# gtop.net
KiCad netlist of a schematic drawn in EAGLE
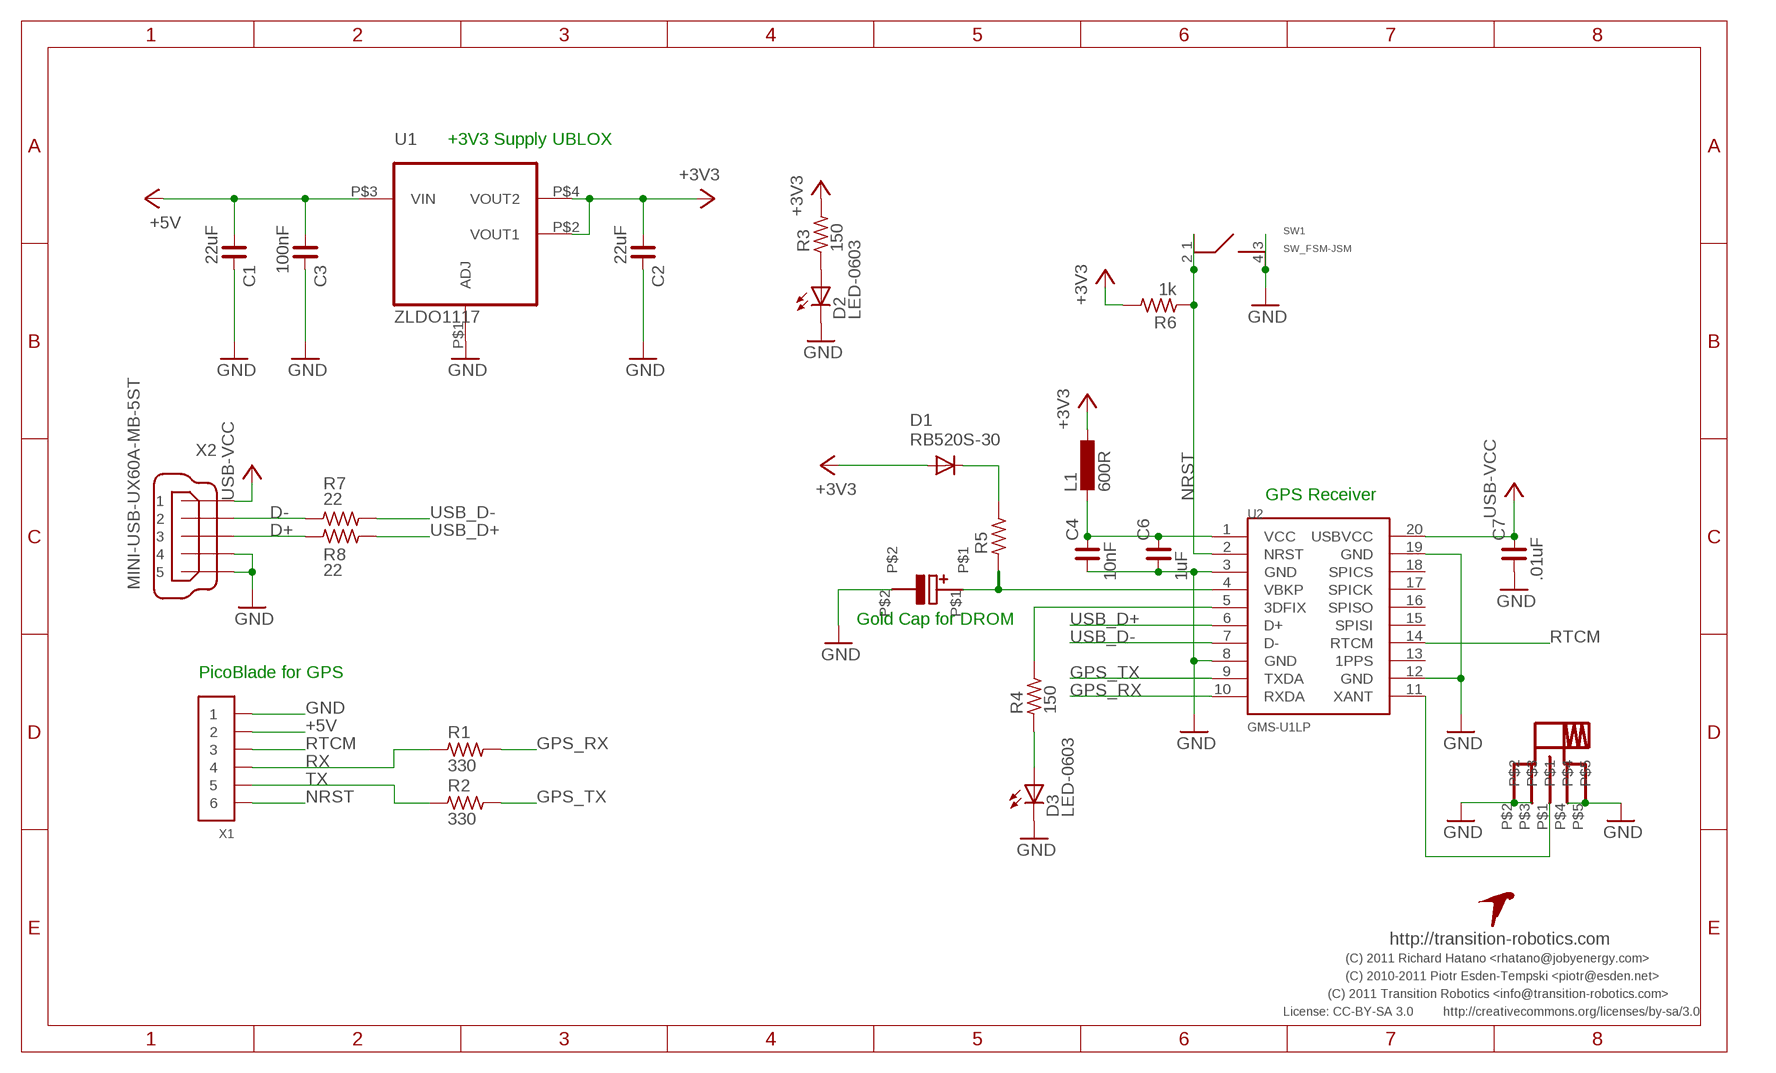
[diagram p0: schematic, sheet 1]

(export (version "E")
  (design (tool "Eeschema 10.0.6"))
  (components
    (comp (ref "C1")
      (value "22uF")
      (footprint "eagle-import:C0805")
      (libsource (lib "eagle-import") (part "C_0805"))
    )
    (comp (ref "C2")
      (value "22uF")
      (footprint "eagle-import:C0805")
      (libsource (lib "eagle-import") (part "C_0805"))
    )
    (comp (ref "C3")
      (value "100nF")
      (footprint "eagle-import:C0805")
      (libsource (lib "eagle-import") (part "C_0805"))
    )
    (comp (ref "C4")
      (value "10nF")
      (footprint "eagle-import:C0603")
      (libsource (lib "eagle-import") (part "C_0603"))
    )
    (comp (ref "C5")
      (value "EECEN0F204AK")
      (footprint "eagle-import:EECEN0F204AK")
      (libsource (lib "eagle-import") (part "EECEN0F204AK"))
    )
    (comp (ref "C6")
      (value "1uF")
      (footprint "eagle-import:C0603")
      (libsource (lib "eagle-import") (part "C_0603"))
    )
    (comp (ref "C7")
      (value ".01uF")
      (footprint "eagle-import:C0603")
      (libsource (lib "eagle-import") (part "C_0603"))
    )
    (comp (ref "D1")
      (value "RB520S-30")
      (footprint "eagle-import:SOD523-DIO")
      (libsource (lib "eagle-import") (part "DIODE"))
    )
    (comp (ref "D2")
      (value "LED-0603")
      (footprint "eagle-import:0603-LED")
      (libsource (lib "eagle-import") (part "LED-0603"))
    )
    (comp (ref "D3")
      (value "LED-0603")
      (footprint "eagle-import:0603-LED")
      (libsource (lib "eagle-import") (part "LED-0603"))
    )
    (comp (ref "J1")
      (value "JOBY_ROBOTICS_SMA")
      (footprint "eagle-import:JOBY_ROBOTICS_SMA")
      (libsource (lib "eagle-import") (part "JOBY_ROBOTICS_SMA"))
    )
    (comp (ref "L1")
      (value "600R")
      (footprint "eagle-import:0603-IND")
      (libsource (lib "eagle-import") (part "INDUCTOR-0603"))
    )
    (comp (ref "R1")
      (value "330")
      (footprint "eagle-import:R0603")
      (libsource (lib "eagle-import") (part "R_0603"))
    )
    (comp (ref "R2")
      (value "330")
      (footprint "eagle-import:R0603")
      (libsource (lib "eagle-import") (part "R_0603"))
    )
    (comp (ref "R3")
      (value "150")
      (footprint "eagle-import:R0603")
      (libsource (lib "eagle-import") (part "R_0603"))
    )
    (comp (ref "R4")
      (value "150")
      (footprint "eagle-import:R0603")
      (libsource (lib "eagle-import") (part "R_0603"))
    )
    (comp (ref "R5")
      (value "R_0603")
      (footprint "eagle-import:R0603")
      (libsource (lib "eagle-import") (part "R_0603"))
    )
    (comp (ref "R6")
      (value "1k")
      (footprint "eagle-import:R0603")
      (libsource (lib "eagle-import") (part "R_0603"))
    )
    (comp (ref "R7")
      (value "22")
      (footprint "eagle-import:R0603")
      (libsource (lib "eagle-import") (part "R_0603"))
    )
    (comp (ref "R8")
      (value "22")
      (footprint "eagle-import:R0603")
      (libsource (lib "eagle-import") (part "R_0603"))
    )
    (comp (ref "SW1")
      (value "SW_FSM-JSM")
      (footprint "eagle-import:SW-FSM_JSM")
      (libsource (lib "eagle-import") (part "SW_FSM-JSM"))
    )
    (comp (ref "U$3")
      (value "TR-LOGO")
      (footprint "eagle-import:TR-LOGO")
      (libsource (lib "eagle-import") (part "TR-LOGO"))
    )
    (comp (ref "U1")
      (value "ZLDO1117")
      (footprint "eagle-import:ZLDO1117")
      (libsource (lib "eagle-import") (part "ZLDO1117"))
    )
    (comp (ref "U2")
      (value "GMS-U1LP")
      (footprint "eagle-import:GMS-U1LP")
      (libsource (lib "eagle-import") (part "GMS-U1LP"))
    )
    (comp (ref "X1")
      (value "CONN_6-1-53261")
      (footprint "eagle-import:PB-53261-06")
      (libsource (lib "eagle-import") (part "CONN_6-1-53261"))
    )
    (comp (ref "X2")
      (value "MINI-USB-UX60A-MB-5ST")
      (footprint "eagle-import:UX60A-MB-5ST")
      (libsource (lib "eagle-import") (part "MINI-USB-UX60A-MB-5ST"))
    )
  )
  (nets
    (net (code "1") (name "+3V3") (class "Default")
      (node (ref "C2") (pin "1") (pinfunction "1_1") (pintype "passive"))
      (node (ref "D1") (pin "2") (pinfunction "A_2") (pintype "passive"))
      (node (ref "L1") (pin "P$1") (pinfunction "1_P$1") (pintype "passive"))
      (node (ref "R3") (pin "2") (pinfunction "2_2") (pintype "passive"))
      (node (ref "R6") (pin "2") (pinfunction "2_2") (pintype "passive"))
      (node (ref "U1") (pin "P$2") (pinfunction "VOUT1_P$2") (pintype "bidirectional"))
      (node (ref "U1") (pin "P$4") (pinfunction "VOUT2_P$4") (pintype "bidirectional"))
    )
    (net (code "2") (name "+5V") (class "Default")
      (node (ref "C1") (pin "1") (pinfunction "1_1") (pintype "passive"))
      (node (ref "C3") (pin "1") (pinfunction "1_1") (pintype "passive"))
      (node (ref "U1") (pin "P$3") (pinfunction "VIN_P$3") (pintype "bidirectional"))
      (node (ref "X1") (pin "2") (pinfunction "2_2") (pintype "bidirectional"))
    )
    (net (code "3") (name "/D+") (class "Default")
      (node (ref "R8") (pin "1") (pinfunction "1_1") (pintype "passive"))
      (node (ref "X2") (pin "3") (pinfunction "3_3") (pintype "input"))
    )
    (net (code "4") (name "/D-") (class "Default")
      (node (ref "R7") (pin "1") (pinfunction "1_1") (pintype "passive"))
      (node (ref "X2") (pin "2") (pinfunction "2_2") (pintype "input"))
    )
    (net (code "5") (name "/GPS_RX") (class "Default")
      (node (ref "R1") (pin "2") (pinfunction "2_2") (pintype "passive"))
      (node (ref "U2") (pin "10") (pinfunction "RXDA_10") (pintype "input"))
    )
    (net (code "6") (name "/GPS_TX") (class "Default")
      (node (ref "R2") (pin "2") (pinfunction "2_2") (pintype "passive"))
      (node (ref "U2") (pin "9") (pinfunction "TXDA_9") (pintype "output"))
    )
    (net (code "7") (name "/NRST") (class "Default")
      (node (ref "R6") (pin "1") (pinfunction "1_1") (pintype "passive"))
      (node (ref "SW1") (pin "1") (pinfunction "1_1") (pintype "bidirectional"))
      (node (ref "SW1") (pin "2") (pinfunction "2_2") (pintype "bidirectional"))
      (node (ref "U2") (pin "2") (pinfunction "NRST_2") (pintype "input"))
      (node (ref "X1") (pin "6") (pinfunction "6_6") (pintype "bidirectional"))
    )
    (net (code "8") (name "/RTCM") (class "Default")
      (node (ref "U2") (pin "14") (pinfunction "RTCM_14") (pintype "input"))
      (node (ref "X1") (pin "3") (pinfunction "3_3") (pintype "bidirectional"))
    )
    (net (code "9") (name "/RX") (class "Default")
      (node (ref "R1") (pin "1") (pinfunction "1_1") (pintype "passive"))
      (node (ref "X1") (pin "4") (pinfunction "4_4") (pintype "bidirectional"))
    )
    (net (code "10") (name "/TX") (class "Default")
      (node (ref "R2") (pin "1") (pinfunction "1_1") (pintype "passive"))
      (node (ref "X1") (pin "5") (pinfunction "5_5") (pintype "bidirectional"))
    )
    (net (code "11") (name "/USB_D+") (class "Default")
      (node (ref "R8") (pin "2") (pinfunction "2_2") (pintype "passive"))
      (node (ref "U2") (pin "6") (pinfunction "D+_6") (pintype "bidirectional"))
    )
    (net (code "12") (name "/USB_D-") (class "Default")
      (node (ref "R7") (pin "2") (pinfunction "2_2") (pintype "passive"))
      (node (ref "U2") (pin "7") (pinfunction "D-_7") (pintype "bidirectional"))
    )
    (net (code "13") (name "GND") (class "Default")
      (node (ref "C1") (pin "2") (pinfunction "2_2") (pintype "passive"))
      (node (ref "C2") (pin "2") (pinfunction "2_2") (pintype "passive"))
      (node (ref "C3") (pin "2") (pinfunction "2_2") (pintype "passive"))
      (node (ref "C4") (pin "1") (pinfunction "1_1") (pintype "passive"))
      (node (ref "C5") (pin "P$2") (pinfunction "P$2_P$2") (pintype "bidirectional"))
      (node (ref "C6") (pin "1") (pinfunction "1_1") (pintype "passive"))
      (node (ref "C7") (pin "1") (pinfunction "1_1") (pintype "passive"))
      (node (ref "D2") (pin "C") (pinfunction "C_C") (pintype "passive"))
      (node (ref "D3") (pin "C") (pinfunction "C_C") (pintype "passive"))
      (node (ref "J1") (pin "P$2") (pinfunction "P$2_P$2") (pintype "bidirectional"))
      (node (ref "J1") (pin "P$3") (pinfunction "P$3_P$3") (pintype "bidirectional"))
      (node (ref "J1") (pin "P$4") (pinfunction "P$4_P$4") (pintype "bidirectional"))
      (node (ref "J1") (pin "P$5") (pinfunction "P$5_P$5") (pintype "bidirectional"))
      (node (ref "SW1") (pin "3") (pinfunction "3_3") (pintype "bidirectional"))
      (node (ref "SW1") (pin "4") (pinfunction "4_4") (pintype "bidirectional"))
      (node (ref "U1") (pin "P$1") (pinfunction "ADJ_P$1") (pintype "bidirectional"))
      (node (ref "U2") (pin "12") (pinfunction "GND_12") (pintype "power_in"))
      (node (ref "U2") (pin "19") (pinfunction "GND_19") (pintype "power_in"))
      (node (ref "U2") (pin "3") (pinfunction "GND_3") (pintype "power_in"))
      (node (ref "U2") (pin "8") (pinfunction "GND_8") (pintype "power_in"))
      (node (ref "X1") (pin "1") (pinfunction "1_1") (pintype "bidirectional"))
      (node (ref "X2") (pin "4") (pinfunction "4_4") (pintype "input"))
      (node (ref "X2") (pin "5") (pinfunction "5_5") (pintype "input"))
    )
    (net (code "14") (name "Net-(D1-C)") (class "Default")
      (node (ref "D1") (pin "1") (pinfunction "C_1") (pintype "passive"))
      (node (ref "R5") (pin "2") (pinfunction "2_2") (pintype "passive"))
    )
    (net (code "15") (name "Net-(D2-PadA)") (class "Default")
      (node (ref "D2") (pin "A") (pinfunction "A_A") (pintype "passive"))
      (node (ref "R3") (pin "1") (pinfunction "1_1") (pintype "passive"))
    )
    (net (code "16") (name "Net-(D3-PadA)") (class "Default")
      (node (ref "D3") (pin "A") (pinfunction "A_A") (pintype "passive"))
      (node (ref "R4") (pin "1") (pinfunction "1_1") (pintype "passive"))
    )
    (net (code "17") (name "Net-(L1-2)") (class "Default")
      (node (ref "C4") (pin "2") (pinfunction "2_2") (pintype "passive"))
      (node (ref "C6") (pin "2") (pinfunction "2_2") (pintype "passive"))
      (node (ref "L1") (pin "P$2") (pinfunction "2_P$2") (pintype "passive"))
      (node (ref "U2") (pin "1") (pinfunction "VCC_1") (pintype "power_in"))
    )
    (net (code "18") (name "Net-(U2-3DFIX)") (class "Default")
      (node (ref "R4") (pin "2") (pinfunction "2_2") (pintype "passive"))
      (node (ref "U2") (pin "5") (pinfunction "3DFIX_5") (pintype "output"))
    )
    (net (code "19") (name "Net-(U2-VBKP)") (class "Default")
      (node (ref "C5") (pin "P$1") (pinfunction "P$1_P$1") (pintype "bidirectional"))
      (node (ref "R5") (pin "1") (pinfunction "1_1") (pintype "passive"))
      (node (ref "U2") (pin "4") (pinfunction "VBKP_4") (pintype "power_in"))
    )
    (net (code "20") (name "Net-(U2-XANT)") (class "Default")
      (node (ref "J1") (pin "P$1") (pinfunction "P$1_P$1") (pintype "bidirectional"))
      (node (ref "U2") (pin "11") (pinfunction "XANT_11") (pintype "input"))
    )
    (net (code "21") (name "USB-VCC") (class "Default")
      (node (ref "C7") (pin "2") (pinfunction "2_2") (pintype "passive"))
      (node (ref "U2") (pin "20") (pinfunction "USBVCC_20") (pintype "power_in"))
      (node (ref "X2") (pin "1") (pinfunction "1_1") (pintype "input"))
    )
    (net (code "22") (name "unconnected-(U2-1PPS-Pad13)") (class "Default")
      (node (ref "U2") (pin "13") (pinfunction "1PPS_13") (pintype "output"))
    )
    (net (code "23") (name "unconnected-(U2-SPICK-Pad17)") (class "Default")
      (node (ref "U2") (pin "17") (pinfunction "SPICK_17") (pintype "input"))
    )
    (net (code "24") (name "unconnected-(U2-SPICS-Pad18)") (class "Default")
      (node (ref "U2") (pin "18") (pinfunction "SPICS_18") (pintype "input"))
    )
    (net (code "25") (name "unconnected-(U2-SPISI-Pad15)") (class "Default")
      (node (ref "U2") (pin "15") (pinfunction "SPISI_15") (pintype "input"))
    )
    (net (code "26") (name "unconnected-(U2-SPISO-Pad16)") (class "Default")
      (node (ref "U2") (pin "16") (pinfunction "SPISO_16") (pintype "output"))
    )
  )
)
